# MCU.net
KiCad netlist of a schematic drawn in Altium Designer
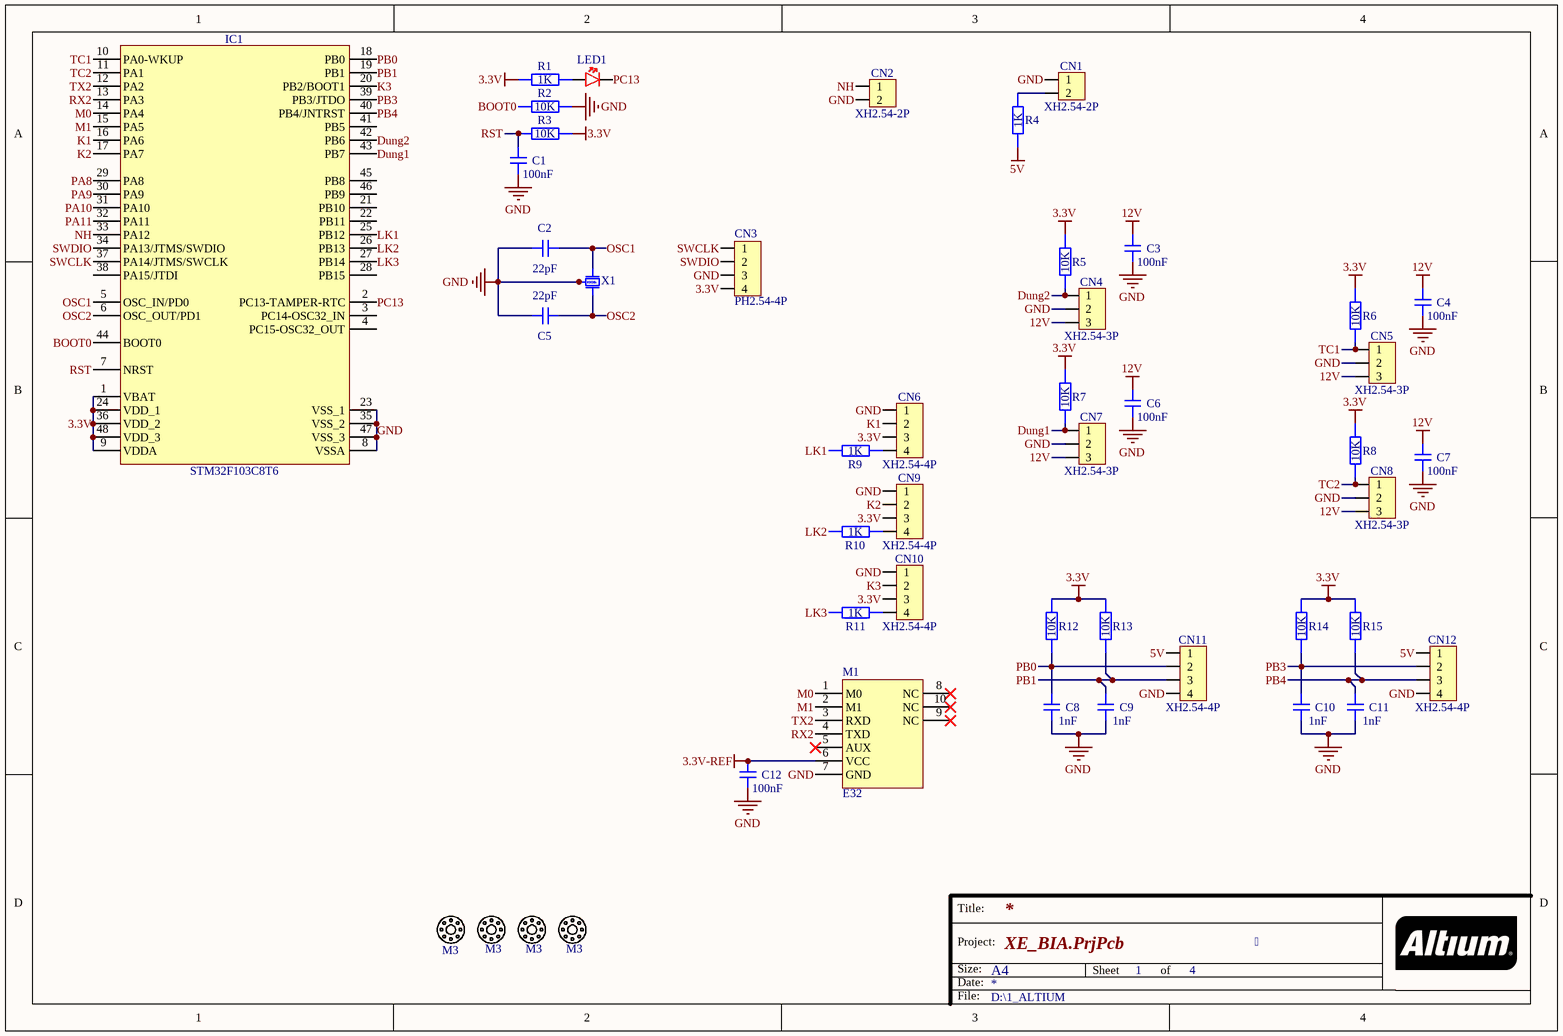
[diagram p0: MCU.SchDoc]

(export (version "E")
  (design (tool "Eeschema 10.0.6"))
  (components
    (comp (ref "1") (value "M3") (footprint "Screw hole M3") (libsource (lib "CbyP") (part "Screw hole M3")))
    (comp (ref "2") (value "M3") (footprint "Screw hole M3") (libsource (lib "CbyP") (part "Screw hole M3")))
    (comp (ref "3") (value "M3") (footprint "Screw hole M3") (libsource (lib "CbyP") (part "Screw hole M3")))
    (comp (ref "4") (value "M3") (footprint "Screw hole M3") (libsource (lib "CbyP") (part "Screw hole M3")))
    (comp (ref "C1")
      (value "100nF")
      (footprint "CAP-0603-2")
      (description "100nF ±10% 50V Ceramic Capacitor X7R 0603")
      (fields (field (name "MANUFACTURER") "Samsung Electro-Mechanics") (field (name "LCSC PART #") "C1591"))
      (libsource (lib "CbyP") (part "CL10B104KB8NNNC"))
    )
    (comp (ref "C2")
      (value "22pF")
      (footprint "CAP-0603-2")
      (description "22pF ±5% 50V Ceramic Capacitor NP0 0603")
      (fields (field (name "MANUFACTURER") "YAGEO") (field (name "LCSC PART #") "C105620"))
      (libsource (lib "CbyP") (part "CC0603JRNPO9BN220"))
    )
    (comp (ref "C3")
      (value "100nF")
      (footprint "CAP-0603-2")
      (description "100nF ±10% 50V Ceramic Capacitor X7R 0603")
      (fields (field (name "MANUFACTURER") "Samsung Electro-Mechanics") (field (name "LCSC PART #") "C1591"))
      (libsource (lib "CbyP") (part "CL10B104KB8NNNC"))
    )
    (comp (ref "C4")
      (value "100nF")
      (footprint "CAP-0603-2")
      (description "100nF ±10% 50V Ceramic Capacitor X7R 0603")
      (fields (field (name "MANUFACTURER") "Samsung Electro-Mechanics") (field (name "LCSC PART #") "C1591"))
      (libsource (lib "CbyP") (part "CL10B104KB8NNNC"))
    )
    (comp (ref "C5")
      (value "22pF")
      (footprint "CAP-0603-2")
      (description "22pF ±5% 50V Ceramic Capacitor NP0 0603")
      (fields (field (name "MANUFACTURER") "YAGEO") (field (name "LCSC PART #") "C105620"))
      (libsource (lib "CbyP") (part "CC0603JRNPO9BN220"))
    )
    (comp (ref "C6")
      (value "100nF")
      (footprint "CAP-0603-2")
      (description "100nF ±10% 50V Ceramic Capacitor X7R 0603")
      (fields (field (name "MANUFACTURER") "Samsung Electro-Mechanics") (field (name "LCSC PART #") "C1591"))
      (libsource (lib "CbyP") (part "CL10B104KB8NNNC"))
    )
    (comp (ref "C7")
      (value "100nF")
      (footprint "CAP-0603-2")
      (description "100nF ±10% 50V Ceramic Capacitor X7R 0603")
      (fields (field (name "MANUFACTURER") "Samsung Electro-Mechanics") (field (name "LCSC PART #") "C1591"))
      (libsource (lib "CbyP") (part "CL10B104KB8NNNC"))
    )
    (comp (ref "C8")
      (value "1nF")
      (footprint "CAP-0603-2")
      (description "1nF ±10% 50V Ceramic Capacitor X7R 0603")
      (fields (field (name "MANUFACTURER") "YAGEO") (field (name "LCSC PART #") "C100040"))
      (libsource (lib "CbyP") (part "CC0603KRX7R9BB102"))
    )
    (comp (ref "C9")
      (value "1nF")
      (footprint "CAP-0603-2")
      (description "1nF ±10% 50V Ceramic Capacitor X7R 0603")
      (fields (field (name "MANUFACTURER") "YAGEO") (field (name "LCSC PART #") "C100040"))
      (libsource (lib "CbyP") (part "CC0603KRX7R9BB102"))
    )
    (comp (ref "C10")
      (value "1nF")
      (footprint "CAP-0603-2")
      (description "1nF ±10% 50V Ceramic Capacitor X7R 0603")
      (fields (field (name "MANUFACTURER") "YAGEO") (field (name "LCSC PART #") "C100040"))
      (libsource (lib "CbyP") (part "CC0603KRX7R9BB102"))
    )
    (comp (ref "C11")
      (value "1nF")
      (footprint "CAP-0603-2")
      (description "1nF ±10% 50V Ceramic Capacitor X7R 0603")
      (fields (field (name "MANUFACTURER") "YAGEO") (field (name "LCSC PART #") "C100040"))
      (libsource (lib "CbyP") (part "CC0603KRX7R9BB102"))
    )
    (comp (ref "C12")
      (value "100nF")
      (footprint "CAP-0603-2")
      (description "100nF ±10% 50V Ceramic Capacitor X7R 0603")
      (fields (field (name "MANUFACTURER") "Samsung Electro-Mechanics") (field (name "LCSC PART #") "C1591"))
      (libsource (lib "CbyP") (part "CL10B104KB8NNNC"))
    )
    (comp (ref "CN1")
      (value "XH2.54-2P")
      (footprint "Plugin,P=2.54mm,2P")
      (description "Connector Header 2 position 2.5mm Pitch 3A Through Hole -25℃~+85℃")
      (fields (field (name "MANUFACTURER") "Bossie") (field (name "MFR.PART #") "BX-XH2.54-2PZZ"))
      (libsource (lib "CbyP") (part "BX-XH2.54-2PZZ"))
    )
    (comp (ref "CN2")
      (value "XH2.54-2P")
      (footprint "Plugin,P=2.54mm,2P")
      (description "Connector Header 2 position 2.5mm Pitch 3A Through Hole -25℃~+85℃")
      (fields (field (name "MANUFACTURER") "Bossie") (field (name "MFR.PART #") "BX-XH2.54-2PZZ"))
      (libsource (lib "CbyP") (part "BX-XH2.54-2PZZ"))
    )
    (comp (ref "CN3")
      (value "PH2.54-4P")
      (footprint "Plugin,P=2.54mm,4P,Pin Headers")
      (description "Pin Header 4 Position 2.54mm Pitch Single Row Through Hole -40℃~+105℃")
      (fields (field (name "MANUFACTURER") "JXTCONN") (field (name "MFR.PART #") "PH2.54-1X4P-H25"))
      (libsource (lib "CbyP") (part "PH2.54-1X4P-H25"))
    )
    (comp (ref "CN4")
      (value "XH2.54-3P")
      (footprint "Plugin,P=2.54mm,3P")
      (description "Connector Header 3 position 2.5mm Pitch 3A Through Hole -25℃~+85℃")
      (fields (field (name "MANUFACTURER") "Bossie") (field (name "MFR.PART #") "BX-XH2.54-3PZZ"))
      (libsource (lib "CbyP") (part "BX-XH2.54-3PZZ"))
    )
    (comp (ref "CN5")
      (value "XH2.54-3P")
      (footprint "Plugin,P=2.54mm,3P")
      (description "Connector Header 3 position 2.5mm Pitch 3A Through Hole -25℃~+85℃")
      (fields (field (name "MANUFACTURER") "Bossie") (field (name "MFR.PART #") "BX-XH2.54-3PZZ"))
      (libsource (lib "CbyP") (part "BX-XH2.54-3PZZ"))
    )
    (comp (ref "CN6")
      (value "XH2.54-4P")
      (footprint "Plugin,P=2.54mm,4P")
      (description "Connector Header 4 position 2.5mm Pitch 3A Through Hole -25℃~+85℃")
      (fields (field (name "MANUFACTURER") "Bossie") (field (name "MFR.PART #") "BX-XH2.54-4PZZ"))
      (libsource (lib "CbyP") (part "BX-XH2.54-4PZZ"))
    )
    (comp (ref "CN7")
      (value "XH2.54-3P")
      (footprint "Plugin,P=2.54mm,3P")
      (description "Connector Header 3 position 2.5mm Pitch 3A Through Hole -25℃~+85℃")
      (fields (field (name "MANUFACTURER") "Bossie") (field (name "MFR.PART #") "BX-XH2.54-3PZZ"))
      (libsource (lib "CbyP") (part "BX-XH2.54-3PZZ"))
    )
    (comp (ref "CN8")
      (value "XH2.54-3P")
      (footprint "Plugin,P=2.54mm,3P")
      (description "Connector Header 3 position 2.5mm Pitch 3A Through Hole -25℃~+85℃")
      (fields (field (name "MANUFACTURER") "Bossie") (field (name "MFR.PART #") "BX-XH2.54-3PZZ"))
      (libsource (lib "CbyP") (part "BX-XH2.54-3PZZ"))
    )
    (comp (ref "CN9")
      (value "XH2.54-4P")
      (footprint "Plugin,P=2.54mm,4P")
      (description "Connector Header 4 position 2.5mm Pitch 3A Through Hole -25℃~+85℃")
      (fields (field (name "MANUFACTURER") "Bossie") (field (name "MFR.PART #") "BX-XH2.54-4PZZ"))
      (libsource (lib "CbyP") (part "BX-XH2.54-4PZZ"))
    )
    (comp (ref "CN10")
      (value "XH2.54-4P")
      (footprint "Plugin,P=2.54mm,4P")
      (description "Connector Header 4 position 2.5mm Pitch 3A Through Hole -25℃~+85℃")
      (fields (field (name "MANUFACTURER") "Bossie") (field (name "MFR.PART #") "BX-XH2.54-4PZZ"))
      (libsource (lib "CbyP") (part "BX-XH2.54-4PZZ"))
    )
    (comp (ref "CN11")
      (value "XH2.54-4P")
      (footprint "Plugin,P=2.54mm,4P")
      (description "Connector Header 4 position 2.5mm Pitch 3A Through Hole -25℃~+85℃")
      (fields (field (name "MANUFACTURER") "Bossie") (field (name "MFR.PART #") "BX-XH2.54-4PZZ"))
      (libsource (lib "CbyP") (part "BX-XH2.54-4PZZ"))
    )
    (comp (ref "CN12")
      (value "XH2.54-4P")
      (footprint "Plugin,P=2.54mm,4P")
      (description "Connector Header 4 position 2.5mm Pitch 3A Through Hole -25℃~+85℃")
      (fields (field (name "MANUFACTURER") "Bossie") (field (name "MFR.PART #") "BX-XH2.54-4PZZ"))
      (libsource (lib "CbyP") (part "BX-XH2.54-4PZZ"))
    )
    (comp (ref "IC1")
      (value "STM32F103C8T6")
      (footprint "LQFP-48(7x7)")
      (description "ARM Cortex-M3 32 Bit 72MHz 37 LQFP-48(7x7) Microcontrollers RoHS")
      (fields (field (name "MANUFACTURER") "ST") (field (name "LCSC PART #") "C8734"))
      (libsource (lib "CbyP") (part "STM32F103C8T6"))
    )
    (comp (ref "LED1")
      (value "RED")
      (footprint "LED-0603")
      (description "25mA 1.8V~2.4V Red 0603 LED Indication - Discrete ROHS")
      (fields (field (name "MANUFACTURER") "YONGYUTAI") (field (name "MFR.PART #") "YLED0603R"))
      (libsource (lib "CbyP") (part "YLED0603R"))
    )
    (comp (ref "M1")
      (value "E32")
      (footprint "E32-TTL-100")
      (fields
        (field (name "MANUFACTURER") "Chengdu Ebyte Electronic")
        (field (name "MFR.PART #") "E32-TTL-100")
        (field (name "LCSC PART #") "NO")
      )
      (libsource (lib "CbyP") (part "E32-TTL-100"))
    )
    (comp (ref "R1")
      (value "1K")
      (footprint "RES-0603-1")
      (description "100mW 1kΩ 75V Thick Film Resistor ±100ppm/℃ ±1% 0603 Chip Resistor - Surface Mount RoHS")
      (fields (field (name "MANUFACTURER") "YAGEO") (field (name "MFR.PART #") "RC0603FR-071KL"))
      (libsource (lib "CbyP") (part "RC0603FR-071KL"))
    )
    (comp (ref "R2")
      (value "10K")
      (footprint "RES-0603-1")
      (description "100mW 10kΩ 75V Thick Film Resistor ±100ppm/℃ ±1% 0603 Chip Resistor - Surface Mount RoHS")
      (fields (field (name "MANUFACTURER") "YAGEO") (field (name "LCSC PART #") "C98220"))
      (libsource (lib "CbyP") (part "RC0603FR-0710KL"))
    )
    (comp (ref "R3")
      (value "10K")
      (footprint "RES-0603-1")
      (description "100mW 10kΩ 75V Thick Film Resistor ±100ppm/℃ ±1% 0603 Chip Resistor - Surface Mount RoHS")
      (fields (field (name "MANUFACTURER") "YAGEO") (field (name "LCSC PART #") "C98220"))
      (libsource (lib "CbyP") (part "RC0603FR-0710KL"))
    )
    (comp (ref "R4")
      (value "1K")
      (footprint "RES-0603-1")
      (description "100mW 1kΩ 75V Thick Film Resistor ±100ppm/℃ ±1% 0603 Chip Resistor - Surface Mount RoHS")
      (fields (field (name "MANUFACTURER") "YAGEO") (field (name "MFR.PART #") "RC0603FR-071KL"))
      (libsource (lib "CbyP") (part "RC0603FR-071KL"))
    )
    (comp (ref "R5")
      (value "10K")
      (footprint "RES-0603-1")
      (description "100mW 10kΩ 75V Thick Film Resistor ±100ppm/℃ ±1% 0603 Chip Resistor - Surface Mount RoHS")
      (fields (field (name "MANUFACTURER") "YAGEO") (field (name "LCSC PART #") "C98220"))
      (libsource (lib "CbyP") (part "RC0603FR-0710KL"))
    )
    (comp (ref "R6")
      (value "10K")
      (footprint "RES-0603-1")
      (description "100mW 10kΩ 75V Thick Film Resistor ±100ppm/℃ ±1% 0603 Chip Resistor - Surface Mount RoHS")
      (fields (field (name "MANUFACTURER") "YAGEO") (field (name "LCSC PART #") "C98220"))
      (libsource (lib "CbyP") (part "RC0603FR-0710KL"))
    )
    (comp (ref "R7")
      (value "10K")
      (footprint "RES-0603-1")
      (description "100mW 10kΩ 75V Thick Film Resistor ±100ppm/℃ ±1% 0603 Chip Resistor - Surface Mount RoHS")
      (fields (field (name "MANUFACTURER") "YAGEO") (field (name "LCSC PART #") "C98220"))
      (libsource (lib "CbyP") (part "RC0603FR-0710KL"))
    )
    (comp (ref "R8")
      (value "10K")
      (footprint "RES-0603-1")
      (description "100mW 10kΩ 75V Thick Film Resistor ±100ppm/℃ ±1% 0603 Chip Resistor - Surface Mount RoHS")
      (fields (field (name "MANUFACTURER") "YAGEO") (field (name "LCSC PART #") "C98220"))
      (libsource (lib "CbyP") (part "RC0603FR-0710KL"))
    )
    (comp (ref "R9")
      (value "1K")
      (footprint "RES-0603-1")
      (description "100mW 1kΩ 75V Thick Film Resistor ±100ppm/℃ ±1% 0603 Chip Resistor - Surface Mount RoHS")
      (fields (field (name "MANUFACTURER") "YAGEO") (field (name "MFR.PART #") "RC0603FR-071KL"))
      (libsource (lib "CbyP") (part "RC0603FR-071KL"))
    )
    (comp (ref "R10")
      (value "1K")
      (footprint "RES-0603-1")
      (description "100mW 1kΩ 75V Thick Film Resistor ±100ppm/℃ ±1% 0603 Chip Resistor - Surface Mount RoHS")
      (fields (field (name "MANUFACTURER") "YAGEO") (field (name "MFR.PART #") "RC0603FR-071KL"))
      (libsource (lib "CbyP") (part "RC0603FR-071KL"))
    )
    (comp (ref "R11")
      (value "1K")
      (footprint "RES-0603-1")
      (description "100mW 1kΩ 75V Thick Film Resistor ±100ppm/℃ ±1% 0603 Chip Resistor - Surface Mount RoHS")
      (fields (field (name "MANUFACTURER") "YAGEO") (field (name "MFR.PART #") "RC0603FR-071KL"))
      (libsource (lib "CbyP") (part "RC0603FR-071KL"))
    )
    (comp (ref "R12")
      (value "10K")
      (footprint "RES-0603-1")
      (description "100mW 10kΩ 75V Thick Film Resistor ±100ppm/℃ ±1% 0603 Chip Resistor - Surface Mount RoHS")
      (fields (field (name "MANUFACTURER") "YAGEO") (field (name "LCSC PART #") "C98220"))
      (libsource (lib "CbyP") (part "RC0603FR-0710KL"))
    )
    (comp (ref "R13")
      (value "10K")
      (footprint "RES-0603-1")
      (description "100mW 10kΩ 75V Thick Film Resistor ±100ppm/℃ ±1% 0603 Chip Resistor - Surface Mount RoHS")
      (fields (field (name "MANUFACTURER") "YAGEO") (field (name "LCSC PART #") "C98220"))
      (libsource (lib "CbyP") (part "RC0603FR-0710KL"))
    )
    (comp (ref "R14")
      (value "10K")
      (footprint "RES-0603-1")
      (description "100mW 10kΩ 75V Thick Film Resistor ±100ppm/℃ ±1% 0603 Chip Resistor - Surface Mount RoHS")
      (fields (field (name "MANUFACTURER") "YAGEO") (field (name "LCSC PART #") "C98220"))
      (libsource (lib "CbyP") (part "RC0603FR-0710KL"))
    )
    (comp (ref "R15")
      (value "10K")
      (footprint "RES-0603-1")
      (description "100mW 10kΩ 75V Thick Film Resistor ±100ppm/℃ ±1% 0603 Chip Resistor - Surface Mount RoHS")
      (fields (field (name "MANUFACTURER") "YAGEO") (field (name "LCSC PART #") "C98220"))
      (libsource (lib "CbyP") (part "RC0603FR-0710KL"))
    )
    (comp (ref "X1")
      (value "8MHz")
      (footprint "SMD5032-4P")
      (description "Crystal 8MHz ±10ppm 20pF SMD5032-4P")
      (fields
        (field (name "MANUFACTURER") "YXC Crystal Oscillators")
        (field (name "MFR.PART #") "X50328MSB4SI")
      )
      (libsource (lib "CbyP") (part "X50328MSB4SI"))
    )
  )
  (nets
    (net (code "1") (name "/BOOT0") (class "Default")
      (node (ref "IC1") (pin "44") (pinfunction "BOOT0_44") (pintype "passive"))
      (node (ref "R2") (pin "1") (pinfunction "1_1") (pintype "passive"))
    )
    (net (code "2") (name "/Dung1") (class "Default")
      (node (ref "CN7") (pin "1") (pinfunction "1_1") (pintype "passive"))
      (node (ref "IC1") (pin "43") (pinfunction "PB7_43") (pintype "passive"))
      (node (ref "R7") (pin "1") (pinfunction "1_1") (pintype "passive"))
    )
    (net (code "3") (name "/Dung2") (class "Default")
      (node (ref "CN4") (pin "1") (pinfunction "1_1") (pintype "passive"))
      (node (ref "IC1") (pin "42") (pinfunction "PB6_42") (pintype "passive"))
      (node (ref "R5") (pin "1") (pinfunction "1_1") (pintype "passive"))
    )
    (net (code "4") (name "/K1") (class "Default")
      (node (ref "CN6") (pin "2") (pinfunction "2_2") (pintype "passive"))
      (node (ref "IC1") (pin "16") (pinfunction "PA6_16") (pintype "passive"))
    )
    (net (code "5") (name "/K2") (class "Default")
      (node (ref "CN9") (pin "2") (pinfunction "2_2") (pintype "passive"))
      (node (ref "IC1") (pin "17") (pinfunction "PA7_17") (pintype "passive"))
    )
    (net (code "6") (name "/K3") (class "Default")
      (node (ref "CN10") (pin "2") (pinfunction "2_2") (pintype "passive"))
      (node (ref "IC1") (pin "20") (pinfunction "PB2/BOOT1_20") (pintype "passive"))
    )
    (net (code "7") (name "/LK1") (class "Default")
      (node (ref "IC1") (pin "25") (pinfunction "PB12_25") (pintype "passive"))
      (node (ref "R9") (pin "1") (pinfunction "1_1") (pintype "passive"))
    )
    (net (code "8") (name "/LK2") (class "Default")
      (node (ref "IC1") (pin "26") (pinfunction "PB13_26") (pintype "passive"))
      (node (ref "R10") (pin "1") (pinfunction "1_1") (pintype "passive"))
    )
    (net (code "9") (name "/LK3") (class "Default")
      (node (ref "IC1") (pin "27") (pinfunction "PB14_27") (pintype "passive"))
      (node (ref "R11") (pin "1") (pinfunction "1_1") (pintype "passive"))
    )
    (net (code "10") (name "/M0") (class "Default")
      (node (ref "IC1") (pin "14") (pinfunction "PA4_14") (pintype "passive"))
      (node (ref "M1") (pin "1") (pinfunction "M0_1") (pintype "passive"))
    )
    (net (code "11") (name "/M1") (class "Default")
      (node (ref "IC1") (pin "15") (pinfunction "PA5_15") (pintype "passive"))
      (node (ref "M1") (pin "2") (pinfunction "M1_2") (pintype "passive"))
    )
    (net (code "12") (name "/NH") (class "Default")
      (node (ref "CN2") (pin "1") (pinfunction "1_1") (pintype "passive"))
      (node (ref "IC1") (pin "33") (pinfunction "PA12_33") (pintype "passive"))
    )
    (net (code "13") (name "/OSC1") (class "Default")
      (node (ref "C2") (pin "1") (pinfunction "1_1") (pintype "passive"))
      (node (ref "IC1") (pin "5") (pinfunction "OSC_IN/PD0_5") (pintype "passive"))
      (node (ref "X1") (pin "1") (pinfunction "1_1") (pintype "passive"))
    )
    (net (code "14") (name "/OSC2") (class "Default")
      (node (ref "C5") (pin "1") (pinfunction "1_1") (pintype "passive"))
      (node (ref "IC1") (pin "6") (pinfunction "OSC_OUT/PD1_6") (pintype "passive"))
      (node (ref "X1") (pin "3") (pinfunction "3_3") (pintype "passive"))
    )
    (net (code "15") (name "/PA8") (class "Default")
      (node (ref "IC1") (pin "29") (pinfunction "PA8_29") (pintype "passive"))
    )
    (net (code "16") (name "/PA9") (class "Default")
      (node (ref "IC1") (pin "30") (pinfunction "PA9_30") (pintype "passive"))
    )
    (net (code "17") (name "/PA10") (class "Default")
      (node (ref "IC1") (pin "31") (pinfunction "PA10_31") (pintype "passive"))
    )
    (net (code "18") (name "/PA11") (class "Default")
      (node (ref "IC1") (pin "32") (pinfunction "PA11_32") (pintype "passive"))
    )
    (net (code "19") (name "/PB0") (class "Default")
      (node (ref "C8") (pin "1") (pinfunction "1_1") (pintype "passive"))
      (node (ref "CN11") (pin "2") (pinfunction "2_2") (pintype "passive"))
      (node (ref "IC1") (pin "18") (pinfunction "PB0_18") (pintype "passive"))
      (node (ref "R12") (pin "1") (pinfunction "1_1") (pintype "passive"))
    )
    (net (code "20") (name "/PB1") (class "Default")
      (node (ref "C9") (pin "1") (pinfunction "1_1") (pintype "passive"))
      (node (ref "CN11") (pin "3") (pinfunction "3_3") (pintype "passive"))
      (node (ref "IC1") (pin "19") (pinfunction "PB1_19") (pintype "passive"))
      (node (ref "R13") (pin "1") (pinfunction "1_1") (pintype "passive"))
    )
    (net (code "21") (name "/PB3") (class "Default")
      (node (ref "C10") (pin "1") (pinfunction "1_1") (pintype "passive"))
      (node (ref "CN12") (pin "2") (pinfunction "2_2") (pintype "passive"))
      (node (ref "IC1") (pin "39") (pinfunction "PB3/JTDO_39") (pintype "passive"))
      (node (ref "R14") (pin "1") (pinfunction "1_1") (pintype "passive"))
    )
    (net (code "22") (name "/PB4") (class "Default")
      (node (ref "C11") (pin "1") (pinfunction "1_1") (pintype "passive"))
      (node (ref "CN12") (pin "3") (pinfunction "3_3") (pintype "passive"))
      (node (ref "IC1") (pin "40") (pinfunction "PB4/JNTRST_40") (pintype "passive"))
      (node (ref "R15") (pin "1") (pinfunction "1_1") (pintype "passive"))
    )
    (net (code "23") (name "/PC13") (class "Default")
      (node (ref "IC1") (pin "2") (pinfunction "PC13-TAMPER-RTC_2") (pintype "passive"))
      (node (ref "LED1") (pin "2") (pinfunction "K_2") (pintype "passive"))
    )
    (net (code "24") (name "/RST") (class "Default")
      (node (ref "C1") (pin "1") (pinfunction "1_1") (pintype "passive"))
      (node (ref "IC1") (pin "7") (pinfunction "NRST_7") (pintype "passive"))
      (node (ref "R3") (pin "1") (pinfunction "1_1") (pintype "passive"))
    )
    (net (code "25") (name "/RX2") (class "Default")
      (node (ref "IC1") (pin "13") (pinfunction "PA3_13") (pintype "passive"))
      (node (ref "M1") (pin "4") (pinfunction "TXD_4") (pintype "passive"))
    )
    (net (code "26") (name "/SWCLK") (class "Default")
      (node (ref "CN3") (pin "1") (pinfunction "1_1") (pintype "passive"))
      (node (ref "IC1") (pin "37") (pinfunction "PA14/JTMS/SWCLK_37") (pintype "passive"))
    )
    (net (code "27") (name "/SWDIO") (class "Default")
      (node (ref "CN3") (pin "2") (pinfunction "2_2") (pintype "passive"))
      (node (ref "IC1") (pin "34") (pinfunction "PA13/JTMS/SWDIO_34") (pintype "passive"))
    )
    (net (code "28") (name "/TC1") (class "Default")
      (node (ref "CN5") (pin "1") (pinfunction "1_1") (pintype "passive"))
      (node (ref "IC1") (pin "10") (pinfunction "PA0-WKUP_10") (pintype "passive"))
      (node (ref "R6") (pin "1") (pinfunction "1_1") (pintype "passive"))
    )
    (net (code "29") (name "/TC2") (class "Default")
      (node (ref "CN8") (pin "1") (pinfunction "1_1") (pintype "passive"))
      (node (ref "IC1") (pin "11") (pinfunction "PA1_11") (pintype "passive"))
      (node (ref "R8") (pin "1") (pinfunction "1_1") (pintype "passive"))
    )
    (net (code "30") (name "/TX2") (class "Default")
      (node (ref "IC1") (pin "12") (pinfunction "PA2_12") (pintype "passive"))
      (node (ref "M1") (pin "3") (pinfunction "RXD_3") (pintype "passive"))
    )
    (net (code "31") (name "3.3V") (class "Default")
      (node (ref "CN10") (pin "3") (pinfunction "3_3") (pintype "passive"))
      (node (ref "CN3") (pin "4") (pinfunction "4_4") (pintype "passive"))
      (node (ref "CN6") (pin "3") (pinfunction "3_3") (pintype "passive"))
      (node (ref "CN9") (pin "3") (pinfunction "3_3") (pintype "passive"))
      (node (ref "IC1") (pin "1") (pinfunction "VBAT_1") (pintype "passive"))
      (node (ref "IC1") (pin "24") (pinfunction "VDD_1_24") (pintype "passive"))
      (node (ref "IC1") (pin "36") (pinfunction "VDD_2_36") (pintype "passive"))
      (node (ref "IC1") (pin "48") (pinfunction "VDD_3_48") (pintype "passive"))
      (node (ref "IC1") (pin "9") (pinfunction "VDDA_9") (pintype "passive"))
      (node (ref "R1") (pin "1") (pinfunction "1_1") (pintype "passive"))
      (node (ref "R12") (pin "2") (pinfunction "2_2") (pintype "passive"))
      (node (ref "R13") (pin "2") (pinfunction "2_2") (pintype "passive"))
      (node (ref "R14") (pin "2") (pinfunction "2_2") (pintype "passive"))
      (node (ref "R15") (pin "2") (pinfunction "2_2") (pintype "passive"))
      (node (ref "R3") (pin "2") (pinfunction "2_2") (pintype "passive"))
      (node (ref "R5") (pin "2") (pinfunction "2_2") (pintype "passive"))
      (node (ref "R6") (pin "2") (pinfunction "2_2") (pintype "passive"))
      (node (ref "R7") (pin "2") (pinfunction "2_2") (pintype "passive"))
      (node (ref "R8") (pin "2") (pinfunction "2_2") (pintype "passive"))
    )
    (net (code "32") (name "3.3V-REF") (class "Default")
      (node (ref "C12") (pin "1") (pinfunction "1_1") (pintype "passive"))
      (node (ref "M1") (pin "6") (pinfunction "VCC_6") (pintype "passive"))
    )
    (net (code "33") (name "5V") (class "Default")
      (node (ref "CN11") (pin "1") (pinfunction "1_1") (pintype "passive"))
      (node (ref "CN12") (pin "1") (pinfunction "1_1") (pintype "passive"))
      (node (ref "R4") (pin "1") (pinfunction "1_1") (pintype "passive"))
    )
    (net (code "34") (name "12V") (class "Default")
      (node (ref "C3") (pin "1") (pinfunction "1_1") (pintype "passive"))
      (node (ref "C4") (pin "1") (pinfunction "1_1") (pintype "passive"))
      (node (ref "C6") (pin "1") (pinfunction "1_1") (pintype "passive"))
      (node (ref "C7") (pin "1") (pinfunction "1_1") (pintype "passive"))
      (node (ref "CN4") (pin "3") (pinfunction "3_3") (pintype "passive"))
      (node (ref "CN5") (pin "3") (pinfunction "3_3") (pintype "passive"))
      (node (ref "CN7") (pin "3") (pinfunction "3_3") (pintype "passive"))
      (node (ref "CN8") (pin "3") (pinfunction "3_3") (pintype "passive"))
    )
    (net (code "35") (name "GND") (class "Default")
      (node (ref "C1") (pin "2") (pinfunction "2_2") (pintype "passive"))
      (node (ref "C10") (pin "2") (pinfunction "2_2") (pintype "passive"))
      (node (ref "C11") (pin "2") (pinfunction "2_2") (pintype "passive"))
      (node (ref "C12") (pin "2") (pinfunction "2_2") (pintype "passive"))
      (node (ref "C2") (pin "2") (pinfunction "2_2") (pintype "passive"))
      (node (ref "C3") (pin "2") (pinfunction "2_2") (pintype "passive"))
      (node (ref "C4") (pin "2") (pinfunction "2_2") (pintype "passive"))
      (node (ref "C5") (pin "2") (pinfunction "2_2") (pintype "passive"))
      (node (ref "C6") (pin "2") (pinfunction "2_2") (pintype "passive"))
      (node (ref "C7") (pin "2") (pinfunction "2_2") (pintype "passive"))
      (node (ref "C8") (pin "2") (pinfunction "2_2") (pintype "passive"))
      (node (ref "C9") (pin "2") (pinfunction "2_2") (pintype "passive"))
      (node (ref "CN1") (pin "1") (pinfunction "1_1") (pintype "passive"))
      (node (ref "CN10") (pin "1") (pinfunction "1_1") (pintype "passive"))
      (node (ref "CN11") (pin "4") (pinfunction "4_4") (pintype "passive"))
      (node (ref "CN12") (pin "4") (pinfunction "4_4") (pintype "passive"))
      (node (ref "CN2") (pin "2") (pinfunction "2_2") (pintype "passive"))
      (node (ref "CN3") (pin "3") (pinfunction "3_3") (pintype "passive"))
      (node (ref "CN4") (pin "2") (pinfunction "2_2") (pintype "passive"))
      (node (ref "CN5") (pin "2") (pinfunction "2_2") (pintype "passive"))
      (node (ref "CN6") (pin "1") (pinfunction "1_1") (pintype "passive"))
      (node (ref "CN7") (pin "2") (pinfunction "2_2") (pintype "passive"))
      (node (ref "CN8") (pin "2") (pinfunction "2_2") (pintype "passive"))
      (node (ref "CN9") (pin "1") (pinfunction "1_1") (pintype "passive"))
      (node (ref "IC1") (pin "23") (pinfunction "VSS_1_23") (pintype "passive"))
      (node (ref "IC1") (pin "35") (pinfunction "VSS_2_35") (pintype "passive"))
      (node (ref "IC1") (pin "47") (pinfunction "VSS_3_47") (pintype "passive"))
      (node (ref "IC1") (pin "8") (pinfunction "VSSA_8") (pintype "passive"))
      (node (ref "M1") (pin "7") (pinfunction "GND_7") (pintype "passive"))
      (node (ref "R2") (pin "2") (pinfunction "2_2") (pintype "passive"))
      (node (ref "X1") (pin "2") (pinfunction "GND_2") (pintype "passive"))
      (node (ref "X1") (pin "4") (pinfunction "GND_4") (pintype "passive"))
    )
    (net (code "36") (name "Net-(CN1-Pad2)") (class "Default")
      (node (ref "CN1") (pin "2") (pinfunction "2_2") (pintype "passive"))
      (node (ref "R4") (pin "2") (pinfunction "2_2") (pintype "passive"))
    )
    (net (code "37") (name "Net-(CN6-Pad4)") (class "Default")
      (node (ref "CN6") (pin "4") (pinfunction "4_4") (pintype "passive"))
      (node (ref "R9") (pin "2") (pinfunction "2_2") (pintype "passive"))
    )
    (net (code "38") (name "Net-(CN9-Pad4)") (class "Default")
      (node (ref "CN9") (pin "4") (pinfunction "4_4") (pintype "passive"))
      (node (ref "R10") (pin "2") (pinfunction "2_2") (pintype "passive"))
    )
    (net (code "39") (name "Net-(CN10-Pad4)") (class "Default")
      (node (ref "CN10") (pin "4") (pinfunction "4_4") (pintype "passive"))
      (node (ref "R11") (pin "2") (pinfunction "2_2") (pintype "passive"))
    )
    (net (code "40") (name "Net-(LED1-A)") (class "Default")
      (node (ref "LED1") (pin "1") (pinfunction "A_1") (pintype "passive"))
      (node (ref "R1") (pin "2") (pinfunction "2_2") (pintype "passive"))
    )
    (net (code "41") (name "unconnected-(IC1-PA15{slash}JTDI-Pad38)") (class "Default")
      (node (ref "IC1") (pin "38") (pinfunction "PA15/JTDI_38") (pintype "passive"))
    )
    (net (code "42") (name "unconnected-(IC1-PB5-Pad41)") (class "Default")
      (node (ref "IC1") (pin "41") (pinfunction "PB5_41") (pintype "passive"))
    )
    (net (code "43") (name "unconnected-(IC1-PB8-Pad45)") (class "Default")
      (node (ref "IC1") (pin "45") (pinfunction "PB8_45") (pintype "passive"))
    )
    (net (code "44") (name "unconnected-(IC1-PB9-Pad46)") (class "Default")
      (node (ref "IC1") (pin "46") (pinfunction "PB9_46") (pintype "passive"))
    )
    (net (code "45") (name "unconnected-(IC1-PB10-Pad21)") (class "Default")
      (node (ref "IC1") (pin "21") (pinfunction "PB10_21") (pintype "passive"))
    )
    (net (code "46") (name "unconnected-(IC1-PB11-Pad22)") (class "Default")
      (node (ref "IC1") (pin "22") (pinfunction "PB11_22") (pintype "passive"))
    )
    (net (code "47") (name "unconnected-(IC1-PB15-Pad28)") (class "Default")
      (node (ref "IC1") (pin "28") (pinfunction "PB15_28") (pintype "passive"))
    )
    (net (code "48") (name "unconnected-(IC1-PC14-OSC32_IN-Pad3)") (class "Default")
      (node (ref "IC1") (pin "3") (pinfunction "PC14-OSC32_IN_3") (pintype "passive"))
    )
    (net (code "49") (name "unconnected-(IC1-PC15-OSC32_OUT-Pad4)") (class "Default")
      (node (ref "IC1") (pin "4") (pinfunction "PC15-OSC32_OUT_4") (pintype "passive"))
    )
    (net (code "50") (name "unconnected-(M1-AUX-Pad5)") (class "Default")
      (node (ref "M1") (pin "5") (pinfunction "AUX_5") (pintype "passive+no_connect"))
    )
    (net (code "51") (name "unconnected-(M1-NC-Pad8)") (class "Default")
      (node (ref "M1") (pin "8") (pinfunction "NC_8") (pintype "passive+no_connect"))
    )
    (net (code "52") (name "unconnected-(M1-NC-Pad9)") (class "Default")
      (node (ref "M1") (pin "9") (pinfunction "NC_9") (pintype "passive+no_connect"))
    )
    (net (code "53") (name "unconnected-(M1-NC-Pad10)") (class "Default")
      (node (ref "M1") (pin "10") (pinfunction "NC_10") (pintype "passive+no_connect"))
    )
  )
)
